# 8051.net
KiCad netlist of a schematic drawn in Altium Designer
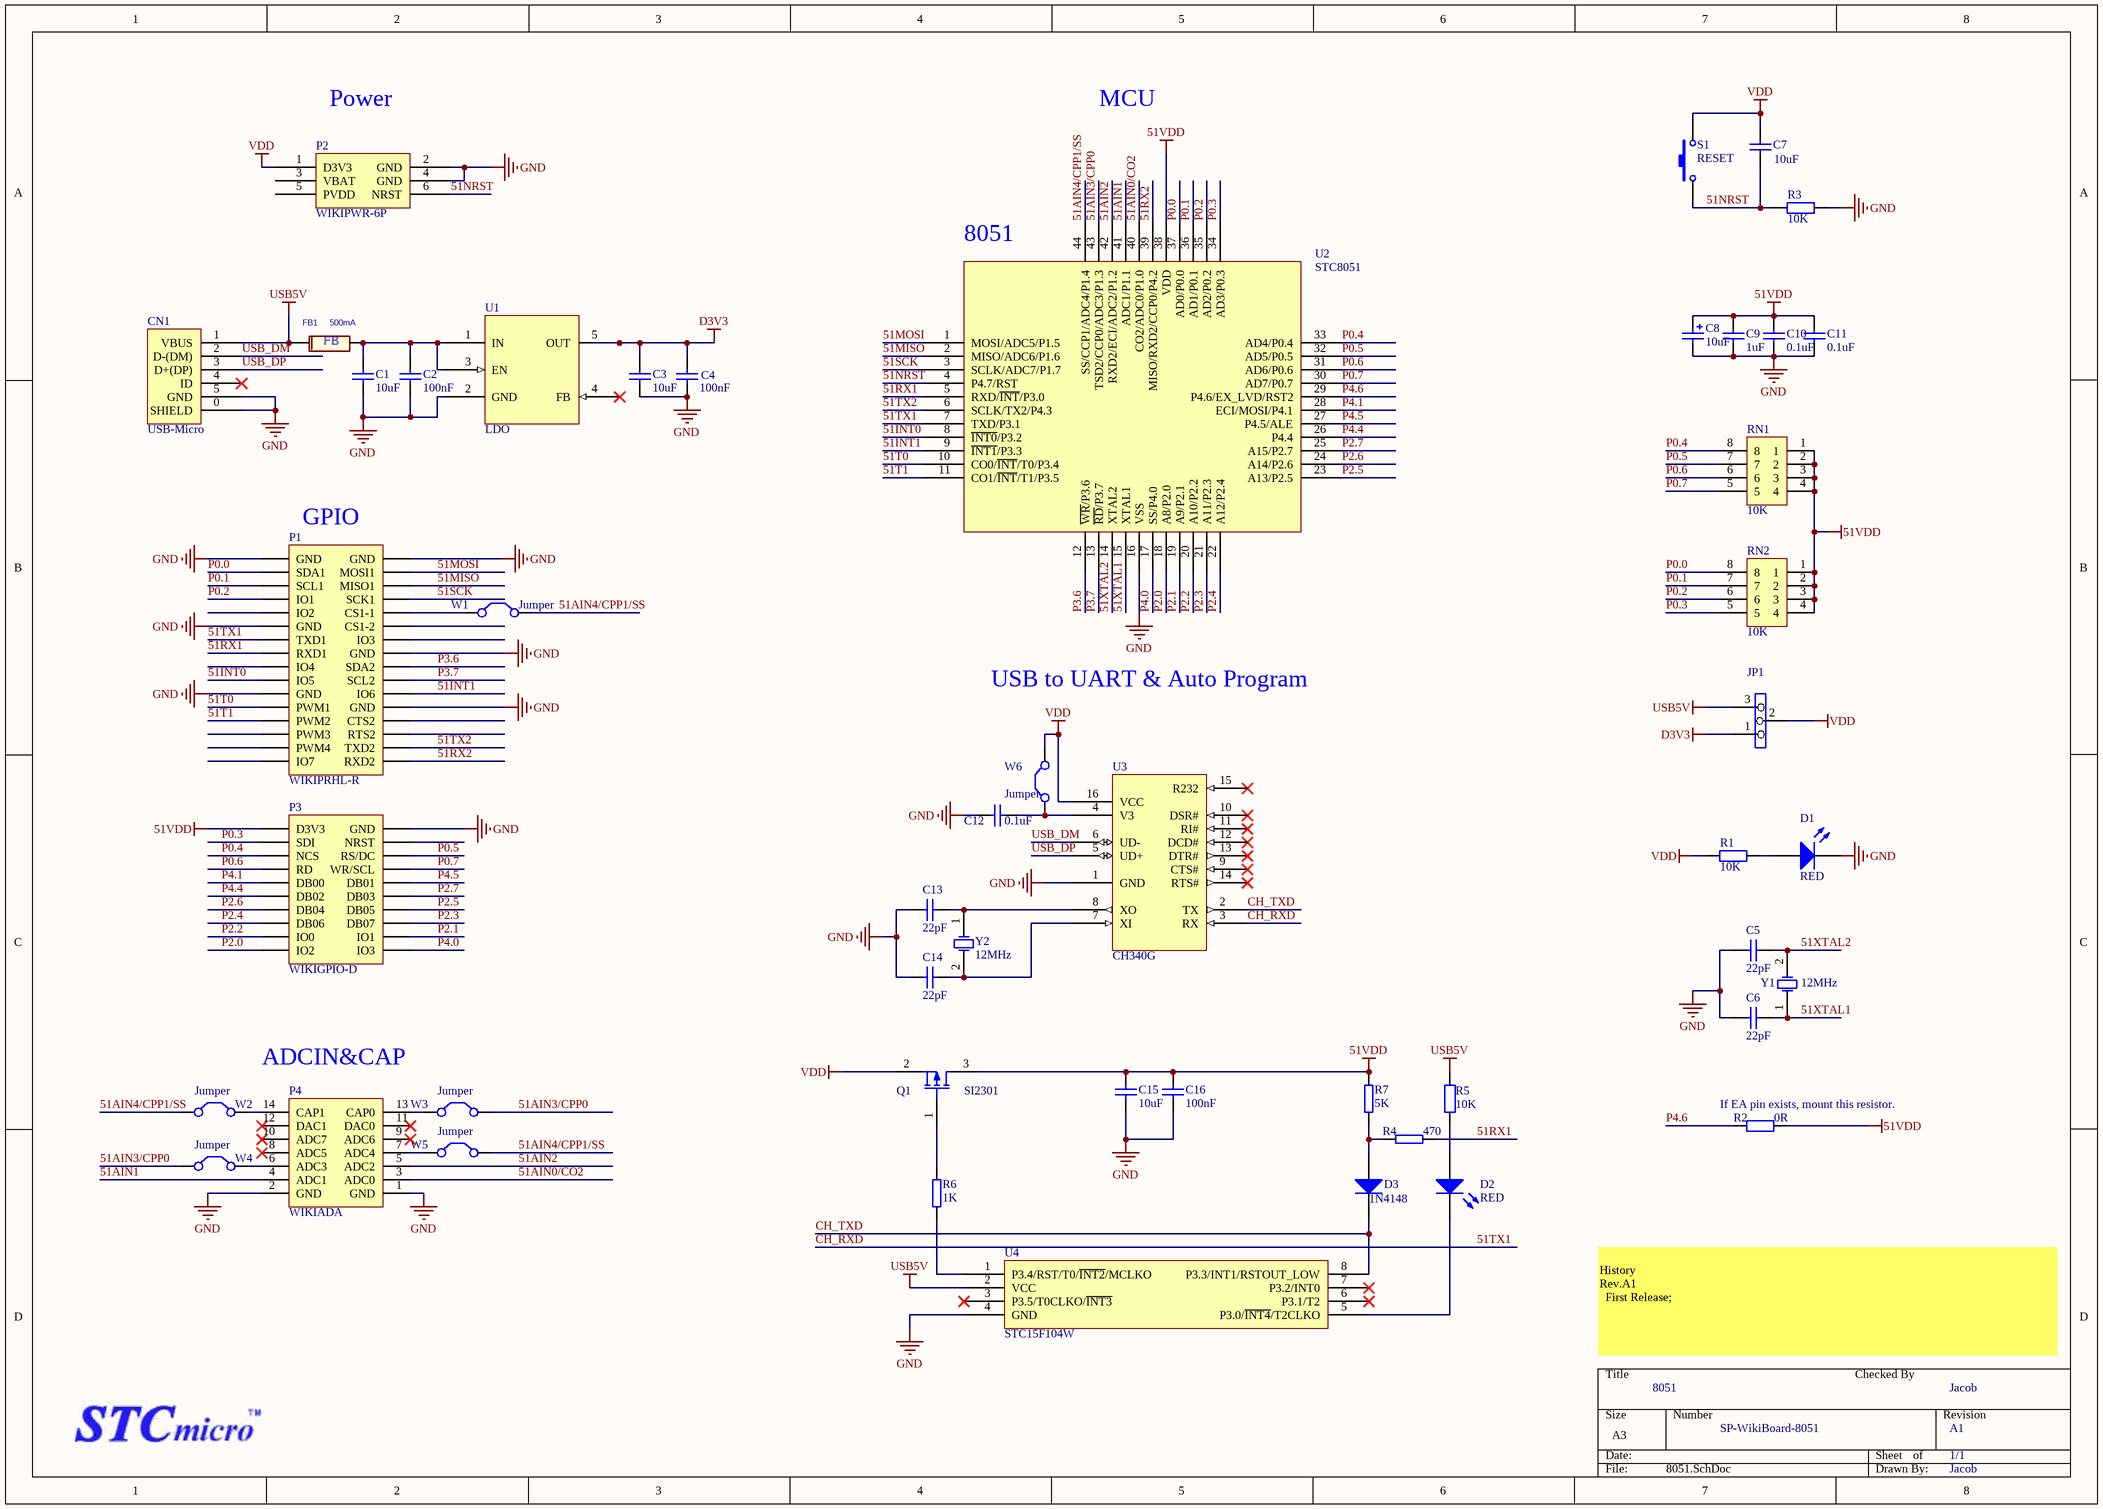
[diagram p0: 8051.SchDoc]

(export (version "E")
  (design (tool "Eeschema 10.0.6"))
  (components
    (comp (ref "C1")
      (value "10uF")
      (footprint "C0805")
      (description "Capacitor")
      (fields (field (name "PUBLISHER") "Altium Limited"))
      (libsource (lib "Miscellaneous Devices") (part "Cap"))
    )
    (comp (ref "C2")
      (value "100nF")
      (footprint "C0603L")
      (description "Capacitor")
      (fields (field (name "PUBLISHER") "Altium Limited"))
      (libsource (lib "Miscellaneous Devices") (part "Cap"))
    )
    (comp (ref "C3")
      (value "10uF")
      (footprint "C0805")
      (description "Capacitor")
      (fields (field (name "PUBLISHER") "Altium Limited"))
      (libsource (lib "Miscellaneous Devices") (part "Cap"))
    )
    (comp (ref "C4")
      (value "100nF")
      (footprint "C0603L")
      (description "Capacitor")
      (fields (field (name "PUBLISHER") "Altium Limited"))
      (libsource (lib "Miscellaneous Devices") (part "Cap"))
    )
    (comp (ref "C5")
      (value "22pF")
      (footprint "C0603L")
      (description "Capacitor")
      (fields (field (name "PUBLISHER") "Altium Limited"))
      (libsource (lib "Miscellaneous Devices") (part "Cap"))
    )
    (comp (ref "C6")
      (value "22pF")
      (footprint "C0603L")
      (description "Capacitor")
      (fields (field (name "PUBLISHER") "Altium Limited"))
      (libsource (lib "Miscellaneous Devices") (part "Cap"))
    )
    (comp (ref "C7")
      (value "10uF")
      (footprint "C0805")
      (description "Capacitor")
      (fields (field (name "PUBLISHER") "Altium Limited"))
      (libsource (lib "Miscellaneous Devices") (part "Cap"))
    )
    (comp (ref "C8")
      (value "10uF")
      (footprint "SMT_C_Tantalum_B")
      (description "Polarized Capacitor (Radial)")
      (fields (field (name "PUBLISHER") "Altium Limited"))
      (libsource (lib "Studio") (part "Cap Pol1"))
    )
    (comp (ref "C9")
      (value "1uF")
      (footprint "C0603L")
      (description "Capacitor")
      (fields (field (name "PUBLISHER") "Altium Limited"))
      (libsource (lib "Miscellaneous Devices") (part "Cap"))
    )
    (comp (ref "C10")
      (value "0.1uF")
      (footprint "C0603L")
      (description "Capacitor")
      (fields (field (name "PUBLISHER") "Altium Limited"))
      (libsource (lib "Miscellaneous Devices") (part "=Value"))
    )
    (comp (ref "C11")
      (value "0.1uF")
      (footprint "C0603L")
      (description "Capacitor")
      (fields (field (name "PUBLISHER") "Altium Limited"))
      (libsource (lib "Miscellaneous Devices") (part "Cap"))
    )
    (comp (ref "C12")
      (value "0.1uF")
      (footprint "C0603L")
      (description "Capacitor")
      (libsource (lib "Studio") (part "Cap"))
    )
    (comp (ref "C13")
      (value "22pF")
      (footprint "C0603L")
      (description "Capacitor")
      (fields (field (name "PUBLISHER") "Altium Limited"))
      (libsource (lib "Miscellaneous Devices") (part "Cap"))
    )
    (comp (ref "C14")
      (value "22pF")
      (footprint "C0603L")
      (description "Capacitor")
      (fields (field (name "PUBLISHER") "Altium Limited"))
      (libsource (lib "Miscellaneous Devices") (part "Cap"))
    )
    (comp (ref "C15")
      (value "10uF")
      (footprint "C0805")
      (description "Capacitor")
      (fields (field (name "PUBLISHER") "Altium Limited"))
      (libsource (lib "Miscellaneous Devices") (part "Cap"))
    )
    (comp (ref "C16")
      (value "100nF")
      (footprint "C0603L")
      (description "Capacitor")
      (fields (field (name "PUBLISHER") "Altium Limited"))
      (libsource (lib "Miscellaneous Devices") (part "Cap"))
    )
    (comp (ref "CN1")
      (value "USB-Micro")
      (footprint "USB_MICRO_5S_B")
      (libsource (lib "Connector") (part "USB-Micro"))
    )
    (comp (ref "D1")
      (value "RED")
      (footprint "SMT_LED_0603")
      (description "Typical INFRARED GaAs LED")
      (fields (field (name "PUBLISHER") "Altium Limited"))
      (libsource (lib "Miscellaneous Devices") (part "LED0"))
    )
    (comp (ref "D2")
      (value "RED")
      (footprint "SMT_LED_0603")
      (description "Typical INFRARED GaAs LED")
      (fields (field (name "PUBLISHER") "Altium Limited"))
      (libsource (lib "Miscellaneous Devices") (part "LED0"))
    )
    (comp (ref "D3")
      (value "1N4148")
      (footprint "SOD80")
      (description "High Conductance Fast Diode")
      (fields (field (name "PUBLISHER") "Altium Limited"))
      (libsource (lib "Misc") (part "Diode 1N4148"))
    )
    (comp (ref "FB1")
      (value "500mA")
      (footprint "R1206")
      (description "Ferrite Beads Inductors Impedance:120Ω±25% Rated Current:1500mA DC Resistance:0.095Ω")
      (fields
        (field (name "MANUFACTURER") "muRata")
        (field (name "MANUFACTURER PART NUMBER") "BLM15EG121SN1")
      )
      (libsource (lib "Mylib") (part "FB"))
    )
    (comp (ref "JP1") (value "JP3") (footprint "SIP3") (libsource (lib "Connector") (part "JP3")))
    (comp (ref "P1")
      (value "WIKIPRHL-R")
      (footprint "WIKIPRHL-R")
      (description "Header, 16-Pin, Dual row")
      (fields (field (name "PUBLISHER") "Altium Limited"))
      (libsource (lib "Connector") (part "WIKIPRHL-R"))
    )
    (comp (ref "P2")
      (value "WIKIPWR-6P")
      (footprint "WIKIPWR-6P")
      (description "PWR HDR")
      (libsource (lib "Connector") (part "WIKIPWR-6P"))
    )
    (comp (ref "P3")
      (value "WIKIGPIO-D")
      (footprint "WIKIGPIO-D")
      (description "Header, 9-Pin, Dual row")
      (fields (field (name "PUBLISHER") "Altium Limited"))
      (libsource (lib "Connector") (part "WIKIGPIO-D"))
    )
    (comp (ref "P4")
      (value "WIKIADA")
      (footprint "WIKIADA")
      (description "Header, 14-Pin, Dual row")
      (libsource (lib "Connector") (part "WIKIADA"))
    )
    (comp (ref "Q1")
      (value "SI2301")
      (footprint "SOT-23A")
      (description "P-Channel MOSFET")
      (fields (field (name "PUBLISHER") "Altium Limited"))
      (libsource (lib "Misc") (part "SI2301"))
    )
    (comp (ref "R1")
      (value "10K")
      (footprint "R0603")
      (description "Resistor")
      (fields (field (name "PUBLISHER") "Altium Limited"))
      (libsource (lib "") (part "Res2_1"))
    )
    (comp (ref "R2")
      (value "0R")
      (footprint "R0603")
      (description "Resistor")
      (fields (field (name "PUBLISHER") "Altium Limited"))
      (libsource (lib "Miscellaneous Devices") (part "Res2"))
    )
    (comp (ref "R3")
      (value "10K")
      (footprint "R0603")
      (description "Resistor")
      (fields (field (name "PUBLISHER") "Altium Limited"))
      (libsource (lib "") (part "Res2_1"))
    )
    (comp (ref "R4")
      (value "470")
      (footprint "R0603")
      (description "Surface mount resistor 0402")
      (libsource (lib "Vowstar_Basic_Device") (part "SMT_R_0402"))
    )
    (comp (ref "R5")
      (value "10K")
      (footprint "R0603")
      (description "Resistor")
      (fields (field (name "PUBLISHER") "Altium Limited"))
      (libsource (lib "") (part "Res2_2"))
    )
    (comp (ref "R6")
      (value "1K")
      (footprint "R0603")
      (description "Surface mount resistor 0402")
      (libsource (lib "Vowstar_Basic_Device") (part "SMT_R_0402"))
    )
    (comp (ref "R7")
      (value "5K")
      (footprint "R0603")
      (description "Surface mount resistor 0402")
      (libsource (lib "Vowstar_Basic_Device") (part "SMT_R_0402"))
    )
    (comp (ref "RN1")
      (value "10K")
      (footprint "RN1X4/0603")
      (description "Res Network")
      (fields (field (name "Comment") "RN4"))
      (libsource (lib "Misc") (part "RN4"))
    )
    (comp (ref "RN2")
      (value "10K")
      (footprint "RN1X4/0603")
      (description "Res Network")
      (fields (field (name "Comment") "RN4"))
      (libsource (lib "Misc") (part "RN4"))
    )
    (comp (ref "S1")
      (value "RESET")
      (footprint "KEY-2x4-SMD")
      (description "Switch")
      (fields (field (name "PUBLISHER") "Altium Limited"))
      (libsource (lib "Miscellaneous Devices") (part "SW-PB"))
    )
    (comp (ref "U1")
      (value "LDO")
      (footprint "SOT23-5")
      (description "General LDO SOT23-5")
      (libsource (lib "Power") (part "LDO-SOT23-5"))
    )
    (comp (ref "U2")
      (value "STC8051")
      (footprint "TQFP44")
      (description "STC12LE5A")
      (libsource (lib "Lunio") (part "STC12LE5A"))
    )
    (comp (ref "U3")
      (value "CH340G")
      (footprint "SO16_M")
      (description "USB to UART IC")
      (libsource (lib "Logic") (part "CH340G"))
    )
    (comp (ref "U4")
      (value "STC15F104W")
      (footprint "SO8_M")
      (libsource (lib "stcmcu") (part "STC15F101W_SOP8_DIP8"))
    )
    (comp (ref "W1")
      (value "Jumper")
      (footprint "Solderbridge")
      (description "Jumper Wire")
      (fields (field (name "PUBLISHER") "Altium Limited"))
      (libsource (lib "Miscellaneous Devices") (part "Jumper"))
    )
    (comp (ref "W2")
      (value "Jumper")
      (footprint "Solderbridge")
      (description "Jumper Wire")
      (fields (field (name "PUBLISHER") "Altium Limited"))
      (libsource (lib "Miscellaneous Devices") (part "Jumper"))
    )
    (comp (ref "W3")
      (value "Jumper")
      (footprint "Solderbridge")
      (description "Jumper Wire")
      (fields (field (name "PUBLISHER") "Altium Limited"))
      (libsource (lib "Miscellaneous Devices") (part "Jumper"))
    )
    (comp (ref "W4")
      (value "Jumper")
      (footprint "Solderbridge")
      (description "Jumper Wire")
      (fields (field (name "PUBLISHER") "Altium Limited"))
      (libsource (lib "Miscellaneous Devices") (part "Jumper"))
    )
    (comp (ref "W5")
      (value "Jumper")
      (footprint "Solderbridge")
      (description "Jumper Wire")
      (fields (field (name "PUBLISHER") "Altium Limited"))
      (libsource (lib "Miscellaneous Devices") (part "Jumper"))
    )
    (comp (ref "W6")
      (value "Jumper")
      (footprint "Solderbridge")
      (description "Jumper Wire")
      (fields (field (name "PUBLISHER") "Altium Limited"))
      (libsource (lib "Miscellaneous Devices") (part "Jumper"))
    )
    (comp (ref "Y1")
      (value "12MHz")
      (footprint "XTAL0602")
      (description "Crystal Oscillator")
      (fields (field (name "PUBLISHER") "Altium Limited"))
      (libsource (lib "Miscellaneous Devices") (part "XTAL"))
    )
    (comp (ref "Y2")
      (value "12MHz")
      (footprint "XTAL_32")
      (description "Crystal Oscillator")
      (fields (field (name "PUBLISHER") "Altium Limited"))
      (libsource (lib "Miscellaneous Devices") (part "XTAL"))
    )
  )
  (nets
    (net (code "1") (name "/51AIN0{slash}CO2") (class "Default")
      (node (ref "P4") (pin "3") (pinfunction "ADC0_3") (pintype "passive"))
      (node (ref "U2") (pin "40") (pinfunction "CO2/ADC0/P1.0_40") (pintype "passive"))
    )
    (net (code "2") (name "/51AIN1") (class "Default")
      (node (ref "P4") (pin "4") (pinfunction "ADC1_4") (pintype "passive"))
      (node (ref "U2") (pin "41") (pinfunction "ADC1/P1.1_41") (pintype "passive"))
    )
    (net (code "3") (name "/51AIN2") (class "Default")
      (node (ref "P4") (pin "5") (pinfunction "ADC2_5") (pintype "passive"))
      (node (ref "U2") (pin "42") (pinfunction "RXD2/ECI/ADC2/P1.2_42") (pintype "passive"))
    )
    (net (code "4") (name "/51AIN3{slash}CPP0") (class "Default")
      (node (ref "U2") (pin "43") (pinfunction "TSD2/CCP0/ADC3/P1.3_43") (pintype "passive"))
      (node (ref "W3") (pin "2") (pinfunction "C2_2") (pintype "passive"))
      (node (ref "W4") (pin "1") (pinfunction "C1_1") (pintype "passive"))
    )
    (net (code "5") (name "/51AIN4{slash}CPP1{slash}SS") (class "Default")
      (node (ref "U2") (pin "44") (pinfunction "SS/CCP1/ADC4/P1.4_44") (pintype "passive"))
      (node (ref "W1") (pin "1") (pinfunction "C1_1") (pintype "passive"))
      (node (ref "W2") (pin "1") (pinfunction "C1_1") (pintype "passive"))
      (node (ref "W5") (pin "2") (pinfunction "C2_2") (pintype "passive"))
    )
    (net (code "6") (name "/51INT0") (class "Default")
      (node (ref "P1") (pin "19") (pinfunction "IO5_19") (pintype "passive"))
      (node (ref "U2") (pin "8") (pinfunction "~{INT0}/P3.2_8") (pintype "passive"))
    )
    (net (code "7") (name "/51INT1") (class "Default")
      (node (ref "P1") (pin "22") (pinfunction "IO6_22") (pintype "passive"))
      (node (ref "U2") (pin "9") (pinfunction "~{INT1}/P3.3_9") (pintype "passive"))
    )
    (net (code "8") (name "/51MISO") (class "Default")
      (node (ref "P1") (pin "6") (pinfunction "MISO1_6") (pintype "passive"))
      (node (ref "U2") (pin "2") (pinfunction "MISO/ADC6/P1.6_2") (pintype "passive"))
    )
    (net (code "9") (name "/51MOSI") (class "Default")
      (node (ref "P1") (pin "4") (pinfunction "MOSI1_4") (pintype "passive"))
      (node (ref "U2") (pin "1") (pinfunction "MOSI/ADC5/P1.5_1") (pintype "passive"))
    )
    (net (code "10") (name "/51NRST") (class "Default")
      (node (ref "C7") (pin "1") (pinfunction "1_1") (pintype "passive"))
      (node (ref "P2") (pin "6") (pinfunction "NRST_6") (pintype "passive"))
      (node (ref "R3") (pin "2") (pinfunction "2_2") (pintype "passive"))
      (node (ref "S1") (pin "1") (pinfunction "1_1") (pintype "passive"))
      (node (ref "U2") (pin "4") (pinfunction "P4.7/RST_4") (pintype "passive"))
    )
    (net (code "11") (name "/51RX1") (class "Default")
      (node (ref "P1") (pin "15") (pinfunction "RXD1_15") (pintype "passive"))
      (node (ref "R4") (pin "2") (pinfunction "2_2") (pintype "passive"))
      (node (ref "U2") (pin "5") (pinfunction "RXD/~{INT}/P3.0_5") (pintype "passive"))
    )
    (net (code "12") (name "/51RX2") (class "Default")
      (node (ref "P1") (pin "32") (pinfunction "RXD2_32") (pintype "passive"))
      (node (ref "U2") (pin "39") (pinfunction "MISO/RXD2/CCP0/P4.2_39") (pintype "passive"))
    )
    (net (code "13") (name "/51SCK") (class "Default")
      (node (ref "P1") (pin "8") (pinfunction "SCK1_8") (pintype "passive"))
      (node (ref "U2") (pin "3") (pinfunction "SCLK/ADC7/P1.7_3") (pintype "passive"))
    )
    (net (code "14") (name "/51T0") (class "Default")
      (node (ref "P1") (pin "23") (pinfunction "PWM1_23") (pintype "passive"))
      (node (ref "U2") (pin "10") (pinfunction "CO0/~{INT}/T0/P3.4_10") (pintype "passive"))
    )
    (net (code "15") (name "/51T1") (class "Default")
      (node (ref "P1") (pin "25") (pinfunction "PWM2_25") (pintype "passive"))
      (node (ref "U2") (pin "11") (pinfunction "CO1/~{INT}/T1/P3.5_11") (pintype "passive"))
    )
    (net (code "16") (name "/51TX1") (class "Default")
      (node (ref "P1") (pin "13") (pinfunction "TXD1_13") (pintype "passive"))
      (node (ref "U2") (pin "7") (pinfunction "TXD/P3.1_7") (pintype "passive"))
      (node (ref "U3") (pin "3") (pinfunction "RX_3") (pintype "input"))
    )
    (net (code "17") (name "/51TX2") (class "Default")
      (node (ref "P1") (pin "30") (pinfunction "TXD2_30") (pintype "passive"))
      (node (ref "U2") (pin "6") (pinfunction "SCLK/TX2/P4.3_6") (pintype "passive"))
    )
    (net (code "18") (name "/51XTAL1") (class "Default")
      (node (ref "C6") (pin "2") (pinfunction "2_2") (pintype "passive"))
      (node (ref "U2") (pin "15") (pinfunction "XTAL1_15") (pintype "passive"))
      (node (ref "Y1") (pin "1") (pinfunction "OSC1_1") (pintype "passive"))
    )
    (net (code "19") (name "/51XTAL2") (class "Default")
      (node (ref "C5") (pin "2") (pinfunction "2_2") (pintype "passive"))
      (node (ref "U2") (pin "14") (pinfunction "XTAL2_14") (pintype "passive"))
      (node (ref "Y1") (pin "2") (pinfunction "OSC2_2") (pintype "passive"))
    )
    (net (code "20") (name "/CH_TXD") (class "Default")
      (node (ref "D3") (pin "2") (pinfunction "K_2") (pintype "passive"))
      (node (ref "U3") (pin "2") (pinfunction "TX_2") (pintype "output"))
      (node (ref "U4") (pin "8") (pinfunction "P3.3/INT1/RSTOUT_LOW_8") (pintype "passive"))
    )
    (net (code "21") (name "/P0.0") (class "Default")
      (node (ref "P1") (pin "3") (pinfunction "SDA1_3") (pintype "passive"))
      (node (ref "RN2") (pin "8") (pinfunction "8_8") (pintype "passive"))
      (node (ref "U2") (pin "37") (pinfunction "AD0/P0.0_37") (pintype "passive"))
    )
    (net (code "22") (name "/P0.1") (class "Default")
      (node (ref "P1") (pin "5") (pinfunction "SCL1_5") (pintype "passive"))
      (node (ref "RN2") (pin "7") (pinfunction "7_7") (pintype "passive"))
      (node (ref "U2") (pin "36") (pinfunction "AD1/P0.1_36") (pintype "passive"))
    )
    (net (code "23") (name "/P0.2") (class "Default")
      (node (ref "P1") (pin "7") (pinfunction "IO1_7") (pintype "passive"))
      (node (ref "RN2") (pin "6") (pinfunction "6_6") (pintype "passive"))
      (node (ref "U2") (pin "35") (pinfunction "AD2/P0.2_35") (pintype "passive"))
    )
    (net (code "24") (name "/P0.3") (class "Default")
      (node (ref "P3") (pin "3") (pinfunction "SDI_3") (pintype "passive"))
      (node (ref "RN2") (pin "5") (pinfunction "5_5") (pintype "passive"))
      (node (ref "U2") (pin "34") (pinfunction "AD3/P0.3_34") (pintype "passive"))
    )
    (net (code "25") (name "/P0.4") (class "Default")
      (node (ref "P3") (pin "5") (pinfunction "NCS_5") (pintype "passive"))
      (node (ref "RN1") (pin "8") (pinfunction "8_8") (pintype "passive"))
      (node (ref "U2") (pin "33") (pinfunction "AD4/P0.4_33") (pintype "passive"))
    )
    (net (code "26") (name "/P0.5") (class "Default")
      (node (ref "P3") (pin "6") (pinfunction "RS/DC_6") (pintype "passive"))
      (node (ref "RN1") (pin "7") (pinfunction "7_7") (pintype "passive"))
      (node (ref "U2") (pin "32") (pinfunction "AD5/P0.5_32") (pintype "passive"))
    )
    (net (code "27") (name "/P0.6") (class "Default")
      (node (ref "P3") (pin "7") (pinfunction "RD_7") (pintype "passive"))
      (node (ref "RN1") (pin "6") (pinfunction "6_6") (pintype "passive"))
      (node (ref "U2") (pin "31") (pinfunction "AD6/P0.6_31") (pintype "passive"))
    )
    (net (code "28") (name "/P0.7") (class "Default")
      (node (ref "P3") (pin "8") (pinfunction "WR/SCL_8") (pintype "passive"))
      (node (ref "RN1") (pin "5") (pinfunction "5_5") (pintype "passive"))
      (node (ref "U2") (pin "30") (pinfunction "AD7/P0.7_30") (pintype "passive"))
    )
    (net (code "29") (name "/P2.0") (class "Default")
      (node (ref "P3") (pin "19") (pinfunction "IO2_19") (pintype "passive"))
      (node (ref "U2") (pin "18") (pinfunction "A8/P2.0_18") (pintype "passive"))
    )
    (net (code "30") (name "/P2.1") (class "Default")
      (node (ref "P3") (pin "18") (pinfunction "IO1_18") (pintype "passive"))
      (node (ref "U2") (pin "19") (pinfunction "A9/P2.1_19") (pintype "passive"))
    )
    (net (code "31") (name "/P2.2") (class "Default")
      (node (ref "P3") (pin "17") (pinfunction "IO0_17") (pintype "passive"))
      (node (ref "U2") (pin "20") (pinfunction "A10/P2.2_20") (pintype "passive"))
    )
    (net (code "32") (name "/P2.3") (class "Default")
      (node (ref "P3") (pin "16") (pinfunction "DB07_16") (pintype "passive"))
      (node (ref "U2") (pin "21") (pinfunction "A11/P2.3_21") (pintype "passive"))
    )
    (net (code "33") (name "/P2.4") (class "Default")
      (node (ref "P3") (pin "15") (pinfunction "DB06_15") (pintype "passive"))
      (node (ref "U2") (pin "22") (pinfunction "A12/P2.4_22") (pintype "passive"))
    )
    (net (code "34") (name "/P2.5") (class "Default")
      (node (ref "P3") (pin "14") (pinfunction "DB05_14") (pintype "passive"))
      (node (ref "U2") (pin "23") (pinfunction "A13/P2.5_23") (pintype "passive"))
    )
    (net (code "35") (name "/P2.6") (class "Default")
      (node (ref "P3") (pin "13") (pinfunction "DB04_13") (pintype "passive"))
      (node (ref "U2") (pin "24") (pinfunction "A14/P2.6_24") (pintype "passive"))
    )
    (net (code "36") (name "/P2.7") (class "Default")
      (node (ref "P3") (pin "12") (pinfunction "DB03_12") (pintype "passive"))
      (node (ref "U2") (pin "25") (pinfunction "A15/P2.7_25") (pintype "passive"))
    )
    (net (code "37") (name "/P3.6") (class "Default")
      (node (ref "P1") (pin "18") (pinfunction "SDA2_18") (pintype "passive"))
      (node (ref "U2") (pin "12") (pinfunction "~{WR}/P3.6_12") (pintype "passive"))
    )
    (net (code "38") (name "/P3.7") (class "Default")
      (node (ref "P1") (pin "20") (pinfunction "SCL2_20") (pintype "passive"))
      (node (ref "U2") (pin "13") (pinfunction "~{RD}/P3.7_13") (pintype "passive"))
    )
    (net (code "39") (name "/P4.0") (class "Default")
      (node (ref "P3") (pin "20") (pinfunction "IO3_20") (pintype "passive"))
      (node (ref "U2") (pin "17") (pinfunction "SS/P4.0_17") (pintype "passive"))
    )
    (net (code "40") (name "/P4.1") (class "Default")
      (node (ref "P3") (pin "9") (pinfunction "DB00_9") (pintype "passive"))
      (node (ref "U2") (pin "28") (pinfunction "ECI/MOSI/P4.1_28") (pintype "passive"))
    )
    (net (code "41") (name "/P4.4") (class "Default")
      (node (ref "P3") (pin "11") (pinfunction "DB02_11") (pintype "passive"))
      (node (ref "U2") (pin "26") (pinfunction "P4.4_26") (pintype "passive"))
    )
    (net (code "42") (name "/P4.5") (class "Default")
      (node (ref "P3") (pin "10") (pinfunction "DB01_10") (pintype "passive"))
      (node (ref "U2") (pin "27") (pinfunction "P4.5/ALE_27") (pintype "passive"))
    )
    (net (code "43") (name "/P4.6") (class "Default")
      (node (ref "R2") (pin "1") (pinfunction "1_1") (pintype "passive"))
      (node (ref "U2") (pin "29") (pinfunction "P4.6/EX_LVD/RST2_29") (pintype "passive"))
    )
    (net (code "44") (name "/USB_DM") (class "Default")
      (node (ref "CN1") (pin "2") (pinfunction "D-(DM)_2") (pintype "passive"))
      (node (ref "U3") (pin "6") (pinfunction "UD-_6") (pintype "bidirectional"))
    )
    (net (code "45") (name "/USB_DP") (class "Default")
      (node (ref "CN1") (pin "3") (pinfunction "D+(DP)_3") (pintype "passive"))
      (node (ref "U3") (pin "5") (pinfunction "UD+_5") (pintype "bidirectional"))
    )
    (net (code "46") (name "51VDD") (class "Default")
      (node (ref "C10") (pin "2") (pinfunction "2_2") (pintype "passive"))
      (node (ref "C11") (pin "2") (pinfunction "2_2") (pintype "passive"))
      (node (ref "C15") (pin "1") (pinfunction "1_1") (pintype "passive"))
      (node (ref "C16") (pin "1") (pinfunction "1_1") (pintype "passive"))
      (node (ref "C8") (pin "1") (pinfunction "1_1") (pintype "passive"))
      (node (ref "C9") (pin "2") (pinfunction "2_2") (pintype "passive"))
      (node (ref "P3") (pin "1") (pinfunction "D3V3_1") (pintype "passive"))
      (node (ref "Q1") (pin "3") (pinfunction "D_3") (pintype "passive"))
      (node (ref "R2") (pin "2") (pinfunction "2_2") (pintype "passive"))
      (node (ref "R7") (pin "1") (pinfunction "1_1") (pintype "passive"))
      (node (ref "RN1") (pin "1") (pinfunction "1_1") (pintype "passive"))
      (node (ref "RN1") (pin "2") (pinfunction "2_2") (pintype "passive"))
      (node (ref "RN1") (pin "3") (pinfunction "3_3") (pintype "passive"))
      (node (ref "RN1") (pin "4") (pinfunction "4_4") (pintype "passive"))
      (node (ref "RN2") (pin "1") (pinfunction "1_1") (pintype "passive"))
      (node (ref "RN2") (pin "2") (pinfunction "2_2") (pintype "passive"))
      (node (ref "RN2") (pin "3") (pinfunction "3_3") (pintype "passive"))
      (node (ref "RN2") (pin "4") (pinfunction "4_4") (pintype "passive"))
      (node (ref "U2") (pin "38") (pinfunction "VDD_38") (pintype "passive"))
    )
    (net (code "47") (name "D3V3") (class "Default")
      (node (ref "C3") (pin "1") (pinfunction "1_1") (pintype "passive"))
      (node (ref "C4") (pin "1") (pinfunction "1_1") (pintype "passive"))
      (node (ref "JP1") (pin "1") (pintype "passive"))
      (node (ref "U1") (pin "5") (pinfunction "OUT_5") (pintype "power_in"))
    )
    (net (code "48") (name "GND") (class "Default")
      (node (ref "C1") (pin "2") (pinfunction "2_2") (pintype "passive"))
      (node (ref "C10") (pin "1") (pinfunction "1_1") (pintype "passive"))
      (node (ref "C11") (pin "1") (pinfunction "1_1") (pintype "passive"))
      (node (ref "C12") (pin "1") (pinfunction "1_1") (pintype "passive"))
      (node (ref "C13") (pin "1") (pinfunction "1_1") (pintype "passive"))
      (node (ref "C14") (pin "1") (pinfunction "1_1") (pintype "passive"))
      (node (ref "C15") (pin "2") (pinfunction "2_2") (pintype "passive"))
      (node (ref "C16") (pin "2") (pinfunction "2_2") (pintype "passive"))
      (node (ref "C2") (pin "2") (pinfunction "2_2") (pintype "passive"))
      (node (ref "C3") (pin "2") (pinfunction "2_2") (pintype "passive"))
      (node (ref "C4") (pin "2") (pinfunction "2_2") (pintype "passive"))
      (node (ref "C5") (pin "1") (pinfunction "1_1") (pintype "passive"))
      (node (ref "C6") (pin "1") (pinfunction "1_1") (pintype "passive"))
      (node (ref "C8") (pin "2") (pinfunction "2_2") (pintype "passive"))
      (node (ref "C9") (pin "1") (pinfunction "1_1") (pintype "passive"))
      (node (ref "CN1") (pin "0") (pinfunction "SHIELD_0") (pintype "passive"))
      (node (ref "CN1") (pin "5") (pinfunction "GND_5") (pintype "passive"))
      (node (ref "D1") (pin "2") (pinfunction "K_2") (pintype "passive"))
      (node (ref "P1") (pin "1") (pinfunction "GND_1") (pintype "passive"))
      (node (ref "P1") (pin "11") (pinfunction "GND_11") (pintype "passive"))
      (node (ref "P1") (pin "16") (pinfunction "GND_16") (pintype "passive"))
      (node (ref "P1") (pin "2") (pinfunction "GND_2") (pintype "passive"))
      (node (ref "P1") (pin "21") (pinfunction "GND_21") (pintype "passive"))
      (node (ref "P1") (pin "24") (pinfunction "GND_24") (pintype "passive"))
      (node (ref "P2") (pin "2") (pinfunction "GND_2") (pintype "passive"))
      (node (ref "P2") (pin "4") (pinfunction "GND_4") (pintype "passive"))
      (node (ref "P3") (pin "2") (pinfunction "GND_2") (pintype "passive"))
      (node (ref "P4") (pin "1") (pinfunction "GND_1") (pintype "passive"))
      (node (ref "P4") (pin "2") (pinfunction "GND_2") (pintype "passive"))
      (node (ref "R3") (pin "1") (pinfunction "1_1") (pintype "passive"))
      (node (ref "U1") (pin "2") (pinfunction "GND_2") (pintype "power_in"))
      (node (ref "U2") (pin "16") (pinfunction "VSS_16") (pintype "passive"))
      (node (ref "U3") (pin "1") (pinfunction "GND_1") (pintype "power_in"))
      (node (ref "U4") (pin "4") (pinfunction "GND_4") (pintype "passive"))
    )
    (net (code "49") (name "Net-(D1-A)") (class "Default")
      (node (ref "D1") (pin "1") (pinfunction "A_1") (pintype "passive"))
      (node (ref "R1") (pin "1") (pinfunction "1_1") (pintype "passive"))
    )
    (net (code "50") (name "Net-(D2-A)") (class "Default")
      (node (ref "D2") (pin "1") (pinfunction "A_1") (pintype "passive"))
      (node (ref "R5") (pin "1") (pinfunction "1_1") (pintype "passive"))
    )
    (net (code "51") (name "Net-(D2-K)") (class "Default")
      (node (ref "D2") (pin "2") (pinfunction "K_2") (pintype "passive"))
      (node (ref "U4") (pin "5") (pinfunction "P3.0/~{INT4}/T2CLKO_5") (pintype "passive"))
    )
    (net (code "52") (name "Net-(D3-A)") (class "Default")
      (node (ref "D3") (pin "1") (pinfunction "A_1") (pintype "passive"))
      (node (ref "R4") (pin "1") (pinfunction "1_1") (pintype "passive"))
      (node (ref "R7") (pin "2") (pinfunction "2_2") (pintype "passive"))
    )
    (net (code "53") (name "Net-(P1-CS1-1)") (class "Default")
      (node (ref "P1") (pin "10") (pinfunction "CS1-1_10") (pintype "passive"))
      (node (ref "W1") (pin "2") (pinfunction "C2_2") (pintype "passive"))
    )
    (net (code "54") (name "Net-(P4-ADC3)") (class "Default")
      (node (ref "P4") (pin "6") (pinfunction "ADC3_6") (pintype "passive"))
      (node (ref "W4") (pin "2") (pinfunction "C2_2") (pintype "passive"))
    )
    (net (code "55") (name "Net-(P4-ADC4)") (class "Default")
      (node (ref "P4") (pin "7") (pinfunction "ADC4_7") (pintype "passive"))
      (node (ref "W5") (pin "1") (pinfunction "C1_1") (pintype "passive"))
    )
    (net (code "56") (name "Net-(P4-CAP0)") (class "Default")
      (node (ref "P4") (pin "13") (pinfunction "CAP0_13") (pintype "passive"))
      (node (ref "W3") (pin "1") (pinfunction "C1_1") (pintype "passive"))
    )
    (net (code "57") (name "Net-(P4-CAP1)") (class "Default")
      (node (ref "P4") (pin "14") (pinfunction "CAP1_14") (pintype "passive"))
      (node (ref "W2") (pin "2") (pinfunction "C2_2") (pintype "passive"))
    )
    (net (code "58") (name "Net-(Q1-G)") (class "Default")
      (node (ref "Q1") (pin "1") (pinfunction "G_1") (pintype "passive"))
      (node (ref "R6") (pin "2") (pinfunction "2_2") (pintype "passive"))
    )
    (net (code "59") (name "Net-(U1-EN)") (class "Default")
      (node (ref "C1") (pin "1") (pinfunction "1_1") (pintype "passive"))
      (node (ref "C2") (pin "1") (pinfunction "1_1") (pintype "passive"))
      (node (ref "FB1") (pin "2") (pinfunction "2_2") (pintype "passive"))
      (node (ref "U1") (pin "1") (pinfunction "IN_1") (pintype "power_in"))
      (node (ref "U1") (pin "3") (pinfunction "EN_3") (pintype "input"))
    )
    (net (code "60") (name "Net-(U3-V3)") (class "Default")
      (node (ref "C12") (pin "2") (pinfunction "2_2") (pintype "passive"))
      (node (ref "U3") (pin "4") (pinfunction "V3_4") (pintype "power_in"))
      (node (ref "W6") (pin "2") (pinfunction "C2_2") (pintype "passive"))
    )
    (net (code "61") (name "Net-(U3-XI)") (class "Default")
      (node (ref "C14") (pin "2") (pinfunction "2_2") (pintype "passive"))
      (node (ref "U3") (pin "7") (pinfunction "XI_7") (pintype "input"))
      (node (ref "Y2") (pin "2") (pinfunction "OSC2_2") (pintype "passive"))
    )
    (net (code "62") (name "Net-(U3-XO)") (class "Default")
      (node (ref "C13") (pin "2") (pinfunction "2_2") (pintype "passive"))
      (node (ref "U3") (pin "8") (pinfunction "XO_8") (pintype "output"))
      (node (ref "Y2") (pin "1") (pinfunction "OSC1_1") (pintype "passive"))
    )
    (net (code "63") (name "Net-(U4-P3.4{slash}RST{slash}T0{slash}~{INT2}{slash}MCLKO)") (class "Default")
      (node (ref "R6") (pin "1") (pinfunction "1_1") (pintype "passive"))
      (node (ref "U4") (pin "1") (pinfunction "P3.4/RST/T0/~{INT2}/MCLKO_1") (pintype "passive"))
    )
    (net (code "64") (name "USB5V") (class "Default")
      (node (ref "CN1") (pin "1") (pinfunction "VBUS_1") (pintype "passive"))
      (node (ref "FB1") (pin "1") (pinfunction "1_1") (pintype "passive"))
      (node (ref "JP1") (pin "3") (pintype "passive"))
      (node (ref "R5") (pin "2") (pinfunction "2_2") (pintype "passive"))
      (node (ref "U4") (pin "2") (pinfunction "VCC_2") (pintype "passive"))
    )
    (net (code "65") (name "VDD") (class "Default")
      (node (ref "C7") (pin "2") (pinfunction "2_2") (pintype "passive"))
      (node (ref "JP1") (pin "2") (pintype "passive"))
      (node (ref "P2") (pin "1") (pinfunction "D3V3_1") (pintype "passive"))
      (node (ref "Q1") (pin "2") (pinfunction "S_2") (pintype "passive"))
      (node (ref "R1") (pin "2") (pinfunction "2_2") (pintype "passive"))
      (node (ref "S1") (pin "2") (pinfunction "2_2") (pintype "passive"))
      (node (ref "U3") (pin "16") (pinfunction "VCC_16") (pintype "power_in"))
      (node (ref "W6") (pin "1") (pinfunction "C1_1") (pintype "passive"))
    )
    (net (code "66") (name "unconnected-(CN1-ID-Pad4)") (class "Default")
      (node (ref "CN1") (pin "4") (pinfunction "ID_4") (pintype "passive+no_connect"))
    )
    (net (code "67") (name "unconnected-(P1-CS1-2-Pad12)") (class "Default")
      (node (ref "P1") (pin "12") (pinfunction "CS1-2_12") (pintype "passive"))
    )
    (net (code "68") (name "unconnected-(P1-CTS2-Pad26)") (class "Default")
      (node (ref "P1") (pin "26") (pinfunction "CTS2_26") (pintype "passive"))
    )
    (net (code "69") (name "unconnected-(P1-IO2-Pad9)") (class "Default")
      (node (ref "P1") (pin "9") (pinfunction "IO2_9") (pintype "passive"))
    )
    (net (code "70") (name "unconnected-(P1-IO3-Pad14)") (class "Default")
      (node (ref "P1") (pin "14") (pinfunction "IO3_14") (pintype "passive"))
    )
    (net (code "71") (name "unconnected-(P1-IO4-Pad17)") (class "Default")
      (node (ref "P1") (pin "17") (pinfunction "IO4_17") (pintype "passive"))
    )
    (net (code "72") (name "unconnected-(P1-IO7-Pad31)") (class "Default")
      (node (ref "P1") (pin "31") (pinfunction "IO7_31") (pintype "passive"))
    )
    (net (code "73") (name "unconnected-(P1-PWM3-Pad27)") (class "Default")
      (node (ref "P1") (pin "27") (pinfunction "PWM3_27") (pintype "passive"))
    )
    (net (code "74") (name "unconnected-(P1-PWM4-Pad29)") (class "Default")
      (node (ref "P1") (pin "29") (pinfunction "PWM4_29") (pintype "passive"))
    )
    (net (code "75") (name "unconnected-(P1-RTS2-Pad28)") (class "Default")
      (node (ref "P1") (pin "28") (pinfunction "RTS2_28") (pintype "passive"))
    )
    (net (code "76") (name "unconnected-(P2-PVDD-Pad5)") (class "Default")
      (node (ref "P2") (pin "5") (pinfunction "PVDD_5") (pintype "passive"))
    )
    (net (code "77") (name "unconnected-(P2-VBAT-Pad3)") (class "Default")
      (node (ref "P2") (pin "3") (pinfunction "VBAT_3") (pintype "passive"))
    )
    (net (code "78") (name "unconnected-(P3-NRST-Pad4)") (class "Default")
      (node (ref "P3") (pin "4") (pinfunction "NRST_4") (pintype "passive"))
    )
    (net (code "79") (name "unconnected-(P4-ADC5-Pad8)") (class "Default")
      (node (ref "P4") (pin "8") (pinfunction "ADC5_8") (pintype "passive+no_connect"))
    )
    (net (code "80") (name "unconnected-(P4-ADC6-Pad9)") (class "Default")
      (node (ref "P4") (pin "9") (pinfunction "ADC6_9") (pintype "passive+no_connect"))
    )
    (net (code "81") (name "unconnected-(P4-ADC7-Pad10)") (class "Default")
      (node (ref "P4") (pin "10") (pinfunction "ADC7_10") (pintype "passive+no_connect"))
    )
    (net (code "82") (name "unconnected-(P4-DAC0-Pad11)") (class "Default")
      (node (ref "P4") (pin "11") (pinfunction "DAC0_11") (pintype "passive+no_connect"))
    )
    (net (code "83") (name "unconnected-(P4-DAC1-Pad12)") (class "Default")
      (node (ref "P4") (pin "12") (pinfunction "DAC1_12") (pintype "passive+no_connect"))
    )
    (net (code "84") (name "unconnected-(U1-FB-Pad4)") (class "Default")
      (node (ref "U1") (pin "4") (pinfunction "FB_4") (pintype "input+no_connect"))
    )
    (net (code "85") (name "unconnected-(U3-CTS#-Pad9)") (class "Default")
      (node (ref "U3") (pin "9") (pinfunction "CTS#_9") (pintype "input+no_connect"))
    )
    (net (code "86") (name "unconnected-(U3-DCD#-Pad12)") (class "Default")
      (node (ref "U3") (pin "12") (pinfunction "DCD#_12") (pintype "input+no_connect"))
    )
    (net (code "87") (name "unconnected-(U3-DSR#-Pad10)") (class "Default")
      (node (ref "U3") (pin "10") (pinfunction "DSR#_10") (pintype "input+no_connect"))
    )
    (net (code "88") (name "unconnected-(U3-DTR#-Pad13)") (class "Default")
      (node (ref "U3") (pin "13") (pinfunction "DTR#_13") (pintype "output+no_connect"))
    )
    (net (code "89") (name "unconnected-(U3-R232-Pad15)") (class "Default")
      (node (ref "U3") (pin "15") (pinfunction "R232_15") (pintype "input+no_connect"))
    )
    (net (code "90") (name "unconnected-(U3-RI#-Pad11)") (class "Default")
      (node (ref "U3") (pin "11") (pinfunction "RI#_11") (pintype "input+no_connect"))
    )
    (net (code "91") (name "unconnected-(U3-RTS#-Pad14)") (class "Default")
      (node (ref "U3") (pin "14") (pinfunction "RTS#_14") (pintype "output+no_connect"))
    )
    (net (code "92") (name "unconnected-(U4-P3.1{slash}T2-Pad6)") (class "Default")
      (node (ref "U4") (pin "6") (pinfunction "P3.1/T2_6") (pintype "passive+no_connect"))
    )
    (net (code "93") (name "unconnected-(U4-P3.2{slash}INT0-Pad7)") (class "Default")
      (node (ref "U4") (pin "7") (pinfunction "P3.2/INT0_7") (pintype "passive+no_connect"))
    )
    (net (code "94") (name "unconnected-(U4-P3.5{slash}T0CLKO{slash}~{INT3}-Pad3)") (class "Default")
      (node (ref "U4") (pin "3") (pinfunction "P3.5/T0CLKO/~{INT3}_3") (pintype "passive+no_connect"))
    )
  )
)
